# PCB_111000_New.net
KiCad netlist of a schematic drawn in EAGLE
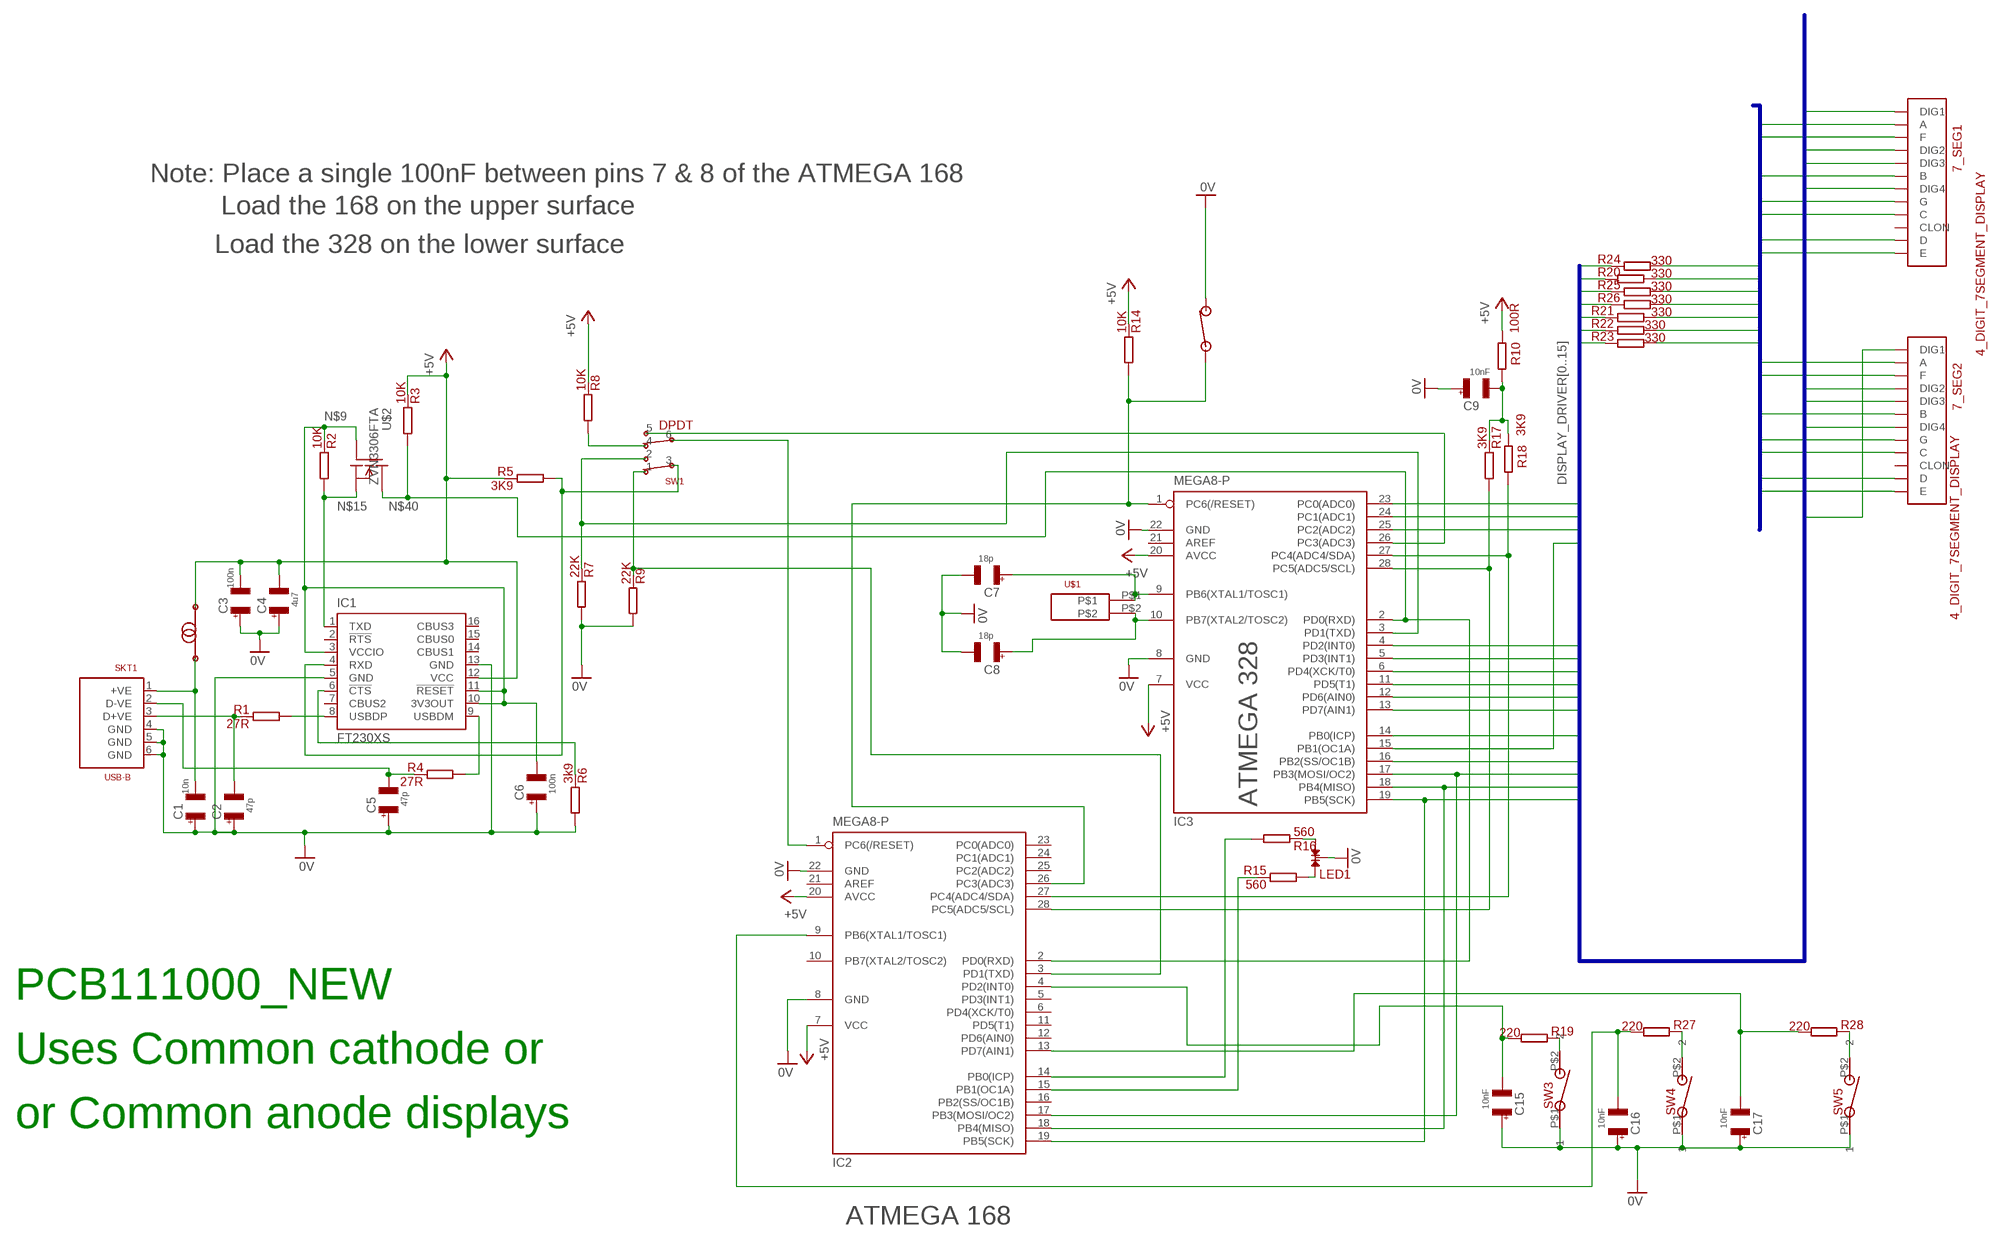
[diagram p0: schematic, sheet 1]

(export (version "E")
  (design (tool "Eeschema 10.0.6"))
  (components
    (comp (ref "7_SEG1")
      (value "4_DIGIT_7SEGMENT_DISPLAY")
      (footprint "eagle-import:4_DIGIT_7SEGMENT_DISPLAY")
      (libsource (lib "eagle-import") (part "4_DIGIT_7SEGMENT_DISPLAY"))
    )
    (comp (ref "7_SEG2")
      (value "4_DIGIT_7SEGMENT_DISPLAY")
      (footprint "eagle-import:4_DIGIT_7SEGMENT_DISPLAY")
      (libsource (lib "eagle-import") (part "4_DIGIT_7SEGMENT_DISPLAY"))
    )
    (comp (ref "C1")
      (value "10n")
      (footprint "eagle-import:1206")
      (libsource (lib "eagle-import") (part "1206C"))
    )
    (comp (ref "C2")
      (value "47p")
      (footprint "eagle-import:1206")
      (libsource (lib "eagle-import") (part "1206C"))
    )
    (comp (ref "C3")
      (value "100n")
      (footprint "eagle-import:1206")
      (libsource (lib "eagle-import") (part "1206C"))
    )
    (comp (ref "C4")
      (value "4u7")
      (footprint "eagle-import:1206")
      (libsource (lib "eagle-import") (part "1206C"))
    )
    (comp (ref "C5")
      (value "47p")
      (footprint "eagle-import:1206")
      (libsource (lib "eagle-import") (part "1206C"))
    )
    (comp (ref "C6")
      (value "100n")
      (footprint "eagle-import:1206")
      (libsource (lib "eagle-import") (part "1206C"))
    )
    (comp (ref "C7")
      (value "18p")
      (footprint "eagle-import:0805")
      (libsource (lib "eagle-import") (part "0805C"))
    )
    (comp (ref "C8")
      (value "18p")
      (footprint "eagle-import:0805")
      (libsource (lib "eagle-import") (part "0805C"))
    )
    (comp (ref "C9")
      (value "10nF")
      (footprint "eagle-import:1206")
      (libsource (lib "eagle-import") (part "1206C"))
    )
    (comp (ref "C15")
      (value "10nF")
      (footprint "eagle-import:1206")
      (libsource (lib "eagle-import") (part "1206C"))
    )
    (comp (ref "C16")
      (value "10nF")
      (footprint "eagle-import:1206")
      (libsource (lib "eagle-import") (part "1206C"))
    )
    (comp (ref "C17")
      (value "10nF")
      (footprint "eagle-import:1206")
      (libsource (lib "eagle-import") (part "1206C"))
    )
    (comp (ref "IC1")
      (value "FT230XS")
      (footprint "eagle-import:SSOP16")
      (libsource (lib "eagle-import") (part "FT230XS"))
    )
    (comp (ref "IC2")
      (value "MEGA8-P")
      (footprint "eagle-import:DIL28-3")
      (libsource (lib "eagle-import") (part "MEGA8-P"))
    )
    (comp (ref "IC3")
      (value "MEGA8-P")
      (footprint "eagle-import:DIL28-3")
      (libsource (lib "eagle-import") (part "MEGA8-P"))
    )
    (comp (ref "L1")
      (value "CHOKE")
      (footprint "eagle-import:1206")
      (libsource (lib "eagle-import") (part "CHOKE"))
    )
    (comp (ref "LED1")
      (value "LED")
      (footprint "eagle-import:CA_DUAL_LED")
      (libsource (lib "eagle-import") (part "LED"))
    )
    (comp (ref "R1")
      (value "27R")
      (footprint "eagle-import:1206")
      (libsource (lib "eagle-import") (part "1206R"))
    )
    (comp (ref "R2")
      (value "10K")
      (footprint "eagle-import:1206")
      (libsource (lib "eagle-import") (part "1206R"))
    )
    (comp (ref "R3")
      (value "10K")
      (footprint "eagle-import:1206")
      (libsource (lib "eagle-import") (part "1206R"))
    )
    (comp (ref "R4")
      (value "27R")
      (footprint "eagle-import:1206")
      (libsource (lib "eagle-import") (part "1206R"))
    )
    (comp (ref "R5")
      (value "3K9")
      (footprint "eagle-import:1206")
      (libsource (lib "eagle-import") (part "1206R"))
    )
    (comp (ref "R6")
      (value "3k9")
      (footprint "eagle-import:1206")
      (libsource (lib "eagle-import") (part "1206R"))
    )
    (comp (ref "R7")
      (value "22K")
      (footprint "eagle-import:1206")
      (libsource (lib "eagle-import") (part "1206R"))
    )
    (comp (ref "R8")
      (value "10K")
      (footprint "eagle-import:1206")
      (libsource (lib "eagle-import") (part "1206R"))
    )
    (comp (ref "R9")
      (value "22K")
      (footprint "eagle-import:1206")
      (libsource (lib "eagle-import") (part "1206R"))
    )
    (comp (ref "R10")
      (value "100R")
      (footprint "eagle-import:1206")
      (libsource (lib "eagle-import") (part "1206R"))
    )
    (comp (ref "R14")
      (value "10K")
      (footprint "eagle-import:1206")
      (libsource (lib "eagle-import") (part "1206R"))
    )
    (comp (ref "R15")
      (value "560")
      (footprint "eagle-import:1206")
      (libsource (lib "eagle-import") (part "1206R"))
    )
    (comp (ref "R16")
      (value "560")
      (footprint "eagle-import:1206")
      (libsource (lib "eagle-import") (part "1206R"))
    )
    (comp (ref "R17")
      (value "3K9")
      (footprint "eagle-import:1206")
      (libsource (lib "eagle-import") (part "1206R"))
    )
    (comp (ref "R18")
      (value "3K9")
      (footprint "eagle-import:1206")
      (libsource (lib "eagle-import") (part "1206R"))
    )
    (comp (ref "R19")
      (value "220")
      (footprint "eagle-import:1206")
      (libsource (lib "eagle-import") (part "1206R"))
    )
    (comp (ref "R20")
      (value "330")
      (footprint "eagle-import:1206")
      (libsource (lib "eagle-import") (part "1206R"))
    )
    (comp (ref "R21")
      (value "330")
      (footprint "eagle-import:1206")
      (libsource (lib "eagle-import") (part "1206R"))
    )
    (comp (ref "R22")
      (value "330")
      (footprint "eagle-import:1206")
      (libsource (lib "eagle-import") (part "1206R"))
    )
    (comp (ref "R23")
      (value "330")
      (footprint "eagle-import:1206")
      (libsource (lib "eagle-import") (part "1206R"))
    )
    (comp (ref "R24")
      (value "330")
      (footprint "eagle-import:1206")
      (libsource (lib "eagle-import") (part "1206R"))
    )
    (comp (ref "R25")
      (value "330")
      (footprint "eagle-import:1206")
      (libsource (lib "eagle-import") (part "1206R"))
    )
    (comp (ref "R26")
      (value "330")
      (footprint "eagle-import:1206")
      (libsource (lib "eagle-import") (part "1206R"))
    )
    (comp (ref "R27")
      (value "220")
      (footprint "eagle-import:1206")
      (libsource (lib "eagle-import") (part "1206R"))
    )
    (comp (ref "R28")
      (value "220")
      (footprint "eagle-import:1206")
      (libsource (lib "eagle-import") (part "1206R"))
    )
    (comp (ref "SKT1")
      (value "USB-B")
      (footprint "eagle-import:USB-B")
      (libsource (lib "eagle-import") (part "USB-B"))
    )
    (comp (ref "SW1")
      (value "DPDT")
      (footprint "eagle-import:DPDT_SWITCH")
      (libsource (lib "eagle-import") (part "DPDT"))
    )
    (comp (ref "SW2")
      (value "NO_SW")
      (footprint "eagle-import:SM_NO_PUSH_BUTTON")
      (libsource (lib "eagle-import") (part "NO_SW"))
    )
    (comp (ref "SW3")
      (value "NO_PB_1")
      (footprint "eagle-import:RE51-0711")
      (libsource (lib "eagle-import") (part "NO_PB_1"))
    )
    (comp (ref "SW4")
      (value "NO_PB_1")
      (footprint "eagle-import:RE51-0711")
      (libsource (lib "eagle-import") (part "NO_PB_1"))
    )
    (comp (ref "SW5")
      (value "NO_PB_1")
      (footprint "eagle-import:RE51-0711")
      (libsource (lib "eagle-import") (part "NO_PB_1"))
    )
    (comp (ref "U$1")
      (value "XTAL")
      (footprint "eagle-import:XTAL_VIAS")
      (libsource (lib "eagle-import") (part "XTAL"))
    )
    (comp (ref "U$2")
      (value "ZVN3306FTA")
      (footprint "eagle-import:SOT-23")
      (libsource (lib "eagle-import") (part "ZVN3306FTA"))
    )
  )
  (nets
    (net (code "2") (name "+5V") (class "Default")
      (node (ref "C3") (pin "P$2") (pinfunction "2_P$2") (pintype "bidirectional"))
      (node (ref "C4") (pin "P$2") (pinfunction "2_P$2") (pintype "bidirectional"))
      (node (ref "IC1") (pin "12") (pinfunction "VCC_12") (pintype "power_in"))
      (node (ref "IC2") (pin "20") (pinfunction "AVCC_20") (pintype "power_in"))
      (node (ref "IC2") (pin "7") (pinfunction "VCC_7") (pintype "power_in"))
      (node (ref "IC3") (pin "20") (pinfunction "AVCC_20") (pintype "power_in"))
      (node (ref "IC3") (pin "7") (pinfunction "VCC_7") (pintype "power_in"))
      (node (ref "L1") (pin "P$2") (pinfunction "2_P$2") (pintype "bidirectional"))
      (node (ref "R10") (pin "P$2") (pinfunction "P$2_P$2") (pintype "bidirectional"))
      (node (ref "R14") (pin "P$2") (pinfunction "P$2_P$2") (pintype "bidirectional"))
      (node (ref "R3") (pin "P$2") (pinfunction "P$2_P$2") (pintype "bidirectional"))
      (node (ref "R5") (pin "P$2") (pinfunction "P$2_P$2") (pintype "bidirectional"))
      (node (ref "R8") (pin "P$2") (pinfunction "P$2_P$2") (pintype "bidirectional"))
    )
    (net (code "3") (name "/DISPLAY_DRIVER0") (class "Default")
      (node (ref "IC3") (pin "15") (pinfunction "PB1(OC1A)_15") (pintype "bidirectional"))
      (node (ref "R24") (pin "P$2") (pinfunction "P$2_P$2") (pintype "bidirectional"))
    )
    (net (code "4") (name "/DISPLAY_DRIVER1") (class "Default")
      (node (ref "IC3") (pin "4") (pinfunction "PD2(INT0)_4") (pintype "bidirectional"))
      (node (ref "R20") (pin "P$2") (pinfunction "P$2_P$2") (pintype "bidirectional"))
    )
    (net (code "5") (name "/DISPLAY_DRIVER2") (class "Default")
      (node (ref "IC3") (pin "5") (pinfunction "PD3(INT1)_5") (pintype "bidirectional"))
      (node (ref "R25") (pin "P$2") (pinfunction "P$2_P$2") (pintype "bidirectional"))
    )
    (net (code "6") (name "/DISPLAY_DRIVER3") (class "Default")
      (node (ref "IC3") (pin "6") (pinfunction "PD4(XCK/T0)_6") (pintype "bidirectional"))
      (node (ref "R26") (pin "P$2") (pinfunction "P$2_P$2") (pintype "bidirectional"))
    )
    (net (code "7") (name "/DISPLAY_DRIVER4") (class "Default")
      (node (ref "IC3") (pin "11") (pinfunction "PD5(T1)_11") (pintype "bidirectional"))
      (node (ref "R21") (pin "P$2") (pinfunction "P$2_P$2") (pintype "bidirectional"))
    )
    (net (code "8") (name "/DISPLAY_DRIVER5") (class "Default")
      (node (ref "IC3") (pin "12") (pinfunction "PD6(AIN0)_12") (pintype "bidirectional"))
      (node (ref "R22") (pin "P$2") (pinfunction "P$2_P$2") (pintype "bidirectional"))
    )
    (net (code "9") (name "/DISPLAY_DRIVER6") (class "Default")
      (node (ref "IC3") (pin "13") (pinfunction "PD7(AIN1)_13") (pintype "bidirectional"))
      (node (ref "R23") (pin "P$2") (pinfunction "P$2_P$2") (pintype "bidirectional"))
    )
    (net (code "10") (name "/DISPLAY_DRIVER8") (class "Default")
      (node (ref "7_SEG2") (pin "P$12") (pinfunction "DIG1_P$12") (pintype "bidirectional"))
      (node (ref "IC3") (pin "14") (pinfunction "PB0(ICP)_14") (pintype "bidirectional"))
    )
    (net (code "11") (name "/DISPLAY_DRIVER9") (class "Default")
      (node (ref "7_SEG2") (pin "P$9") (pinfunction "DIG2_P$9") (pintype "bidirectional"))
      (node (ref "IC3") (pin "16") (pinfunction "PB2(SS/OC1B)_16") (pintype "bidirectional"))
    )
    (net (code "12") (name "/DISPLAY_DRIVER10") (class "Default")
      (node (ref "7_SEG2") (pin "P$8") (pinfunction "DIG3_P$8") (pintype "bidirectional"))
      (node (ref "IC2") (pin "17") (pinfunction "PB3(MOSI/OC2)_17") (pintype "bidirectional"))
      (node (ref "IC3") (pin "17") (pinfunction "PB3(MOSI/OC2)_17") (pintype "bidirectional"))
    )
    (net (code "13") (name "/DISPLAY_DRIVER11") (class "Default")
      (node (ref "7_SEG2") (pin "P$6") (pinfunction "DIG4_P$6") (pintype "bidirectional"))
      (node (ref "IC2") (pin "18") (pinfunction "PB4(MISO)_18") (pintype "bidirectional"))
      (node (ref "IC3") (pin "18") (pinfunction "PB4(MISO)_18") (pintype "bidirectional"))
    )
    (net (code "14") (name "/DISPLAY_DRIVER12") (class "Default")
      (node (ref "7_SEG1") (pin "P$12") (pinfunction "DIG1_P$12") (pintype "bidirectional"))
      (node (ref "IC2") (pin "19") (pinfunction "PB5(SCK)_19") (pintype "bidirectional"))
      (node (ref "IC3") (pin "19") (pinfunction "PB5(SCK)_19") (pintype "bidirectional"))
    )
    (net (code "15") (name "/DISPLAY_DRIVER13") (class "Default")
      (node (ref "7_SEG1") (pin "P$9") (pinfunction "DIG2_P$9") (pintype "bidirectional"))
      (node (ref "IC3") (pin "23") (pinfunction "PC0(ADC0)_23") (pintype "bidirectional"))
    )
    (net (code "16") (name "/DISPLAY_DRIVER14") (class "Default")
      (node (ref "7_SEG1") (pin "P$8") (pinfunction "DIG3_P$8") (pintype "bidirectional"))
      (node (ref "IC3") (pin "24") (pinfunction "PC1(ADC1)_24") (pintype "bidirectional"))
    )
    (net (code "17") (name "/DISPLAY_DRIVER15") (class "Default")
      (node (ref "7_SEG1") (pin "P$6") (pinfunction "DIG4_P$6") (pintype "bidirectional"))
      (node (ref "IC3") (pin "25") (pinfunction "PC2(ADC2)_25") (pintype "bidirectional"))
    )
    (net (code "19") (name "/N$9") (class "Default")
      (node (ref "C6") (pin "P$2") (pinfunction "2_P$2") (pintype "bidirectional"))
      (node (ref "IC1") (pin "10") (pinfunction "3V3OUT_10") (pintype "output"))
      (node (ref "IC1") (pin "11") (pinfunction "~{RESET}_11") (pintype "input"))
      (node (ref "IC1") (pin "3") (pinfunction "VCCIO_3") (pintype "power_in"))
      (node (ref "R2") (pin "P$2") (pinfunction "P$2_P$2") (pintype "bidirectional"))
      (node (ref "U$2") (pin "3") (pinfunction "G_3") (pintype "passive"))
    )
    (net (code "20") (name "/N$15") (class "Default")
      (node (ref "IC1") (pin "1") (pinfunction "TXD_1") (pintype "output"))
      (node (ref "R2") (pin "P$1") (pinfunction "P$1_P$1") (pintype "bidirectional"))
      (node (ref "U$2") (pin "2") (pinfunction "S_2") (pintype "passive"))
    )
    (net (code "21") (name "/N$40") (class "Default")
      (node (ref "IC2") (pin "2") (pinfunction "PD0(RXD)_2") (pintype "bidirectional"))
      (node (ref "IC3") (pin "2") (pinfunction "PD0(RXD)_2") (pintype "bidirectional"))
      (node (ref "R3") (pin "P$1") (pinfunction "P$1_P$1") (pintype "bidirectional"))
      (node (ref "U$2") (pin "1") (pinfunction "D_1") (pintype "passive"))
    )
    (net (code "22") (name "/SEVEN_SEG0") (class "Default")
      (node (ref "7_SEG1") (pin "P$11") (pinfunction "A_P$11") (pintype "bidirectional"))
      (node (ref "7_SEG2") (pin "P$11") (pinfunction "A_P$11") (pintype "bidirectional"))
      (node (ref "R24") (pin "P$1") (pinfunction "P$1_P$1") (pintype "bidirectional"))
    )
    (net (code "23") (name "/SEVEN_SEG1") (class "Default")
      (node (ref "7_SEG1") (pin "P$7") (pinfunction "B_P$7") (pintype "bidirectional"))
      (node (ref "7_SEG2") (pin "P$7") (pinfunction "B_P$7") (pintype "bidirectional"))
      (node (ref "R20") (pin "P$1") (pinfunction "P$1_P$1") (pintype "bidirectional"))
    )
    (net (code "24") (name "/SEVEN_SEG2") (class "Default")
      (node (ref "7_SEG1") (pin "P$4") (pinfunction "C_P$4") (pintype "bidirectional"))
      (node (ref "7_SEG2") (pin "P$4") (pinfunction "C_P$4") (pintype "bidirectional"))
      (node (ref "R25") (pin "P$1") (pinfunction "P$1_P$1") (pintype "bidirectional"))
    )
    (net (code "25") (name "/SEVEN_SEG3") (class "Default")
      (node (ref "7_SEG1") (pin "P$2") (pinfunction "D_P$2") (pintype "bidirectional"))
      (node (ref "7_SEG2") (pin "P$2") (pinfunction "D_P$2") (pintype "bidirectional"))
      (node (ref "R26") (pin "P$1") (pinfunction "P$1_P$1") (pintype "bidirectional"))
    )
    (net (code "26") (name "/SEVEN_SEG4") (class "Default")
      (node (ref "7_SEG1") (pin "P$1") (pinfunction "E_P$1") (pintype "bidirectional"))
      (node (ref "7_SEG2") (pin "P$1") (pinfunction "E_P$1") (pintype "bidirectional"))
      (node (ref "R21") (pin "P$1") (pinfunction "P$1_P$1") (pintype "bidirectional"))
    )
    (net (code "27") (name "/SEVEN_SEG5") (class "Default")
      (node (ref "7_SEG1") (pin "P$10") (pinfunction "F_P$10") (pintype "bidirectional"))
      (node (ref "7_SEG2") (pin "P$10") (pinfunction "F_P$10") (pintype "bidirectional"))
      (node (ref "R22") (pin "P$1") (pinfunction "P$1_P$1") (pintype "bidirectional"))
    )
    (net (code "28") (name "/SEVEN_SEG6") (class "Default")
      (node (ref "7_SEG1") (pin "P$5") (pinfunction "G_P$5") (pintype "bidirectional"))
      (node (ref "7_SEG2") (pin "P$5") (pinfunction "G_P$5") (pintype "bidirectional"))
      (node (ref "R23") (pin "P$1") (pinfunction "P$1_P$1") (pintype "bidirectional"))
    )
    (net (code "29") (name "0V") (class "Default")
      (node (ref "C1") (pin "P$1") (pinfunction "1_P$1") (pintype "bidirectional"))
      (node (ref "C15") (pin "P$1") (pinfunction "1_P$1") (pintype "bidirectional"))
      (node (ref "C16") (pin "P$1") (pinfunction "1_P$1") (pintype "bidirectional"))
      (node (ref "C17") (pin "P$1") (pinfunction "1_P$1") (pintype "bidirectional"))
      (node (ref "C2") (pin "P$1") (pinfunction "1_P$1") (pintype "bidirectional"))
      (node (ref "C3") (pin "P$1") (pinfunction "1_P$1") (pintype "bidirectional"))
      (node (ref "C4") (pin "P$1") (pinfunction "1_P$1") (pintype "bidirectional"))
      (node (ref "C5") (pin "P$1") (pinfunction "1_P$1") (pintype "bidirectional"))
      (node (ref "C6") (pin "P$1") (pinfunction "1_P$1") (pintype "bidirectional"))
      (node (ref "C7") (pin "2") (pinfunction "2_2") (pintype "bidirectional"))
      (node (ref "C8") (pin "2") (pinfunction "2_2") (pintype "bidirectional"))
      (node (ref "C9") (pin "P$1") (pinfunction "1_P$1") (pintype "bidirectional"))
      (node (ref "IC1") (pin "13") (pinfunction "GND_13") (pintype "power_in"))
      (node (ref "IC1") (pin "5") (pinfunction "GND_5") (pintype "power_in"))
      (node (ref "IC2") (pin "22") (pinfunction "GND_22") (pintype "power_in"))
      (node (ref "IC2") (pin "8") (pinfunction "GND_8") (pintype "power_in"))
      (node (ref "IC3") (pin "22") (pinfunction "GND_22") (pintype "power_in"))
      (node (ref "IC3") (pin "8") (pinfunction "GND_8") (pintype "power_in"))
      (node (ref "LED1") (pin "2") (pinfunction "2_2") (pintype "bidirectional"))
      (node (ref "R6") (pin "P$1") (pinfunction "P$1_P$1") (pintype "bidirectional"))
      (node (ref "R7") (pin "P$1") (pinfunction "P$1_P$1") (pintype "bidirectional"))
      (node (ref "R9") (pin "P$1") (pinfunction "P$1_P$1") (pintype "bidirectional"))
      (node (ref "SKT1") (pin "4") (pinfunction "GND_4") (pintype "bidirectional"))
      (node (ref "SKT1") (pin "5") (pinfunction "GND_5") (pintype "bidirectional"))
      (node (ref "SKT1") (pin "6") (pinfunction "GND_6") (pintype "bidirectional"))
      (node (ref "SW2") (pin "P$2") (pinfunction "2_P$2") (pintype "bidirectional"))
      (node (ref "SW3") (pin "P$1") (pinfunction "1_P$1") (pintype "bidirectional"))
      (node (ref "SW4") (pin "P$1") (pinfunction "1_P$1") (pintype "bidirectional"))
      (node (ref "SW5") (pin "P$1") (pinfunction "1_P$1") (pintype "bidirectional"))
    )
    (net (code "30") (name "Net-(C1-2)") (class "Default")
      (node (ref "C1") (pin "P$2") (pinfunction "2_P$2") (pintype "bidirectional"))
      (node (ref "L1") (pin "P$1") (pinfunction "1_P$1") (pintype "bidirectional"))
      (node (ref "SKT1") (pin "1") (pinfunction "+VE_1") (pintype "bidirectional"))
    )
    (net (code "31") (name "Net-(C2-2)") (class "Default")
      (node (ref "C2") (pin "P$2") (pinfunction "2_P$2") (pintype "bidirectional"))
      (node (ref "R1") (pin "P$2") (pinfunction "P$2_P$2") (pintype "bidirectional"))
      (node (ref "SKT1") (pin "3") (pinfunction "D+VE_3") (pintype "bidirectional"))
    )
    (net (code "32") (name "Net-(C5-2)") (class "Default")
      (node (ref "C5") (pin "P$2") (pinfunction "2_P$2") (pintype "bidirectional"))
      (node (ref "R4") (pin "P$2") (pinfunction "P$2_P$2") (pintype "bidirectional"))
      (node (ref "SKT1") (pin "2") (pinfunction "D-VE_2") (pintype "bidirectional"))
    )
    (net (code "33") (name "Net-(C9-2)") (class "Default")
      (node (ref "C9") (pin "P$2") (pinfunction "2_P$2") (pintype "bidirectional"))
      (node (ref "R10") (pin "P$1") (pinfunction "P$1_P$1") (pintype "bidirectional"))
      (node (ref "R17") (pin "P$2") (pinfunction "P$2_P$2") (pintype "bidirectional"))
      (node (ref "R18") (pin "P$2") (pinfunction "P$2_P$2") (pintype "bidirectional"))
    )
    (net (code "34") (name "Net-(C15-2)") (class "Default")
      (node (ref "C15") (pin "P$2") (pinfunction "2_P$2") (pintype "bidirectional"))
      (node (ref "IC2") (pin "4") (pinfunction "PD2(INT0)_4") (pintype "bidirectional"))
      (node (ref "R19") (pin "P$1") (pinfunction "P$1_P$1") (pintype "bidirectional"))
    )
    (net (code "35") (name "Net-(C16-2)") (class "Default")
      (node (ref "C16") (pin "P$2") (pinfunction "2_P$2") (pintype "bidirectional"))
      (node (ref "IC2") (pin "9") (pinfunction "PB6(XTAL1/TOSC1)_9") (pintype "bidirectional"))
      (node (ref "R27") (pin "P$1") (pinfunction "P$1_P$1") (pintype "bidirectional"))
    )
    (net (code "36") (name "Net-(C17-2)") (class "Default")
      (node (ref "C17") (pin "P$2") (pinfunction "2_P$2") (pintype "bidirectional"))
      (node (ref "IC2") (pin "13") (pinfunction "PD7(AIN1)_13") (pintype "bidirectional"))
      (node (ref "R28") (pin "P$1") (pinfunction "P$1_P$1") (pintype "bidirectional"))
    )
    (net (code "37") (name "Net-(IC1-RXD)") (class "Default")
      (node (ref "IC1") (pin "4") (pinfunction "RXD_4") (pintype "input"))
      (node (ref "R5") (pin "P$1") (pinfunction "P$1_P$1") (pintype "bidirectional"))
      (node (ref "SW1") (pin "3") (pinfunction "3_3") (pintype "bidirectional"))
    )
    (net (code "38") (name "Net-(IC1-USBDM)") (class "Default")
      (node (ref "IC1") (pin "9") (pinfunction "USBDM_9") (pintype "input"))
      (node (ref "R4") (pin "P$1") (pinfunction "P$1_P$1") (pintype "bidirectional"))
    )
    (net (code "39") (name "Net-(IC1-USBDP)") (class "Default")
      (node (ref "IC1") (pin "8") (pinfunction "USBDP_8") (pintype "input"))
      (node (ref "R1") (pin "P$1") (pinfunction "P$1_P$1") (pintype "bidirectional"))
    )
    (net (code "40") (name "Net-(IC1-~{CTS})") (class "Default")
      (node (ref "IC1") (pin "6") (pinfunction "~{CTS}_6") (pintype "input"))
      (node (ref "R6") (pin "P$2") (pinfunction "P$2_P$2") (pintype "bidirectional"))
    )
    (net (code "41") (name "Net-(IC2-PB0(ICP))") (class "Default")
      (node (ref "IC2") (pin "14") (pinfunction "PB0(ICP)_14") (pintype "bidirectional"))
      (node (ref "R16") (pin "P$1") (pinfunction "P$1_P$1") (pintype "bidirectional"))
    )
    (net (code "42") (name "Net-(IC2-PB1(OC1A))") (class "Default")
      (node (ref "IC2") (pin "15") (pinfunction "PB1(OC1A)_15") (pintype "bidirectional"))
      (node (ref "R15") (pin "P$2") (pinfunction "P$2_P$2") (pintype "bidirectional"))
    )
    (net (code "43") (name "Net-(IC2-PC3(ADC3))") (class "Default")
      (node (ref "IC2") (pin "26") (pinfunction "PC3(ADC3)_26") (pintype "bidirectional"))
      (node (ref "IC3") (pin "1") (pinfunction "PC6(/RESET)_1") (pintype "bidirectional"))
      (node (ref "R14") (pin "P$1") (pinfunction "P$1_P$1") (pintype "bidirectional"))
      (node (ref "SW2") (pin "P$1") (pinfunction "1_P$1") (pintype "bidirectional"))
    )
    (net (code "44") (name "Net-(IC2-PC4(ADC4{slash}SDA))") (class "Default")
      (node (ref "IC2") (pin "27") (pinfunction "PC4(ADC4/SDA)_27") (pintype "bidirectional"))
      (node (ref "IC3") (pin "27") (pinfunction "PC4(ADC4/SDA)_27") (pintype "bidirectional"))
      (node (ref "R18") (pin "P$1") (pinfunction "P$1_P$1") (pintype "bidirectional"))
    )
    (net (code "45") (name "Net-(IC2-PC5(ADC5{slash}SCL))") (class "Default")
      (node (ref "IC2") (pin "28") (pinfunction "PC5(ADC5/SCL)_28") (pintype "bidirectional"))
      (node (ref "IC3") (pin "28") (pinfunction "PC5(ADC5/SCL)_28") (pintype "bidirectional"))
      (node (ref "R17") (pin "P$1") (pinfunction "P$1_P$1") (pintype "bidirectional"))
    )
    (net (code "46") (name "Net-(IC2-PC6({slash}RESET))") (class "Default")
      (node (ref "IC2") (pin "1") (pinfunction "PC6(/RESET)_1") (pintype "bidirectional"))
      (node (ref "SW1") (pin "6") (pinfunction "6_6") (pintype "bidirectional"))
    )
    (net (code "47") (name "Net-(IC2-PD1(TXD))") (class "Default")
      (node (ref "IC2") (pin "3") (pinfunction "PD1(TXD)_3") (pintype "bidirectional"))
      (node (ref "R9") (pin "P$2") (pinfunction "P$2_P$2") (pintype "bidirectional"))
      (node (ref "SW1") (pin "1") (pinfunction "1_1") (pintype "bidirectional"))
    )
    (net (code "48") (name "Net-(IC3-PB6(XTAL1{slash}TOSC1))") (class "Default")
      (node (ref "C7") (pin "1") (pinfunction "1_1") (pintype "bidirectional"))
      (node (ref "IC3") (pin "9") (pinfunction "PB6(XTAL1/TOSC1)_9") (pintype "bidirectional"))
      (node (ref "U$1") (pin "P$1") (pinfunction "P$1_P$1") (pintype "bidirectional"))
    )
    (net (code "49") (name "Net-(IC3-PB7(XTAL2{slash}TOSC2))") (class "Default")
      (node (ref "C8") (pin "1") (pinfunction "1_1") (pintype "bidirectional"))
      (node (ref "IC3") (pin "10") (pinfunction "PB7(XTAL2/TOSC2)_10") (pintype "bidirectional"))
      (node (ref "U$1") (pin "P$2") (pinfunction "P$2_P$2") (pintype "bidirectional"))
    )
    (net (code "50") (name "Net-(IC3-PC3(ADC3))") (class "Default")
      (node (ref "IC3") (pin "26") (pinfunction "PC3(ADC3)_26") (pintype "bidirectional"))
      (node (ref "SW1") (pin "5") (pinfunction "5_5") (pintype "bidirectional"))
    )
    (net (code "51") (name "Net-(IC3-PD1(TXD))") (class "Default")
      (node (ref "IC3") (pin "3") (pinfunction "PD1(TXD)_3") (pintype "bidirectional"))
      (node (ref "R7") (pin "P$2") (pinfunction "P$2_P$2") (pintype "bidirectional"))
      (node (ref "SW1") (pin "2") (pinfunction "2_2") (pintype "bidirectional"))
    )
    (net (code "52") (name "Net-(LED1-Pad1)") (class "Default")
      (node (ref "LED1") (pin "1") (pinfunction "1_1") (pintype "bidirectional"))
      (node (ref "R15") (pin "P$1") (pinfunction "P$1_P$1") (pintype "bidirectional"))
    )
    (net (code "53") (name "Net-(LED1-Pad3)") (class "Default")
      (node (ref "LED1") (pin "3") (pinfunction "3_3") (pintype "bidirectional"))
      (node (ref "R16") (pin "P$2") (pinfunction "P$2_P$2") (pintype "bidirectional"))
    )
    (net (code "54") (name "Net-(R8-PadP$1)") (class "Default")
      (node (ref "R8") (pin "P$1") (pinfunction "P$1_P$1") (pintype "bidirectional"))
      (node (ref "SW1") (pin "4") (pinfunction "4_4") (pintype "bidirectional"))
    )
    (net (code "55") (name "Net-(SW3-2)") (class "Default")
      (node (ref "R19") (pin "P$2") (pinfunction "P$2_P$2") (pintype "bidirectional"))
      (node (ref "SW3") (pin "P$2") (pinfunction "2_P$2") (pintype "bidirectional"))
    )
    (net (code "56") (name "Net-(SW4-2)") (class "Default")
      (node (ref "R27") (pin "P$2") (pinfunction "P$2_P$2") (pintype "bidirectional"))
      (node (ref "SW4") (pin "P$2") (pinfunction "2_P$2") (pintype "bidirectional"))
    )
    (net (code "57") (name "Net-(SW5-2)") (class "Default")
      (node (ref "R28") (pin "P$2") (pinfunction "P$2_P$2") (pintype "bidirectional"))
      (node (ref "SW5") (pin "P$2") (pinfunction "2_P$2") (pintype "bidirectional"))
    )
    (net (code "58") (name "unconnected-(7_SEG1-CLON-PadP$3)") (class "Default")
      (node (ref "7_SEG1") (pin "P$3") (pinfunction "CLON_P$3") (pintype "bidirectional"))
    )
    (net (code "59") (name "unconnected-(7_SEG2-CLON-PadP$3)") (class "Default")
      (node (ref "7_SEG2") (pin "P$3") (pinfunction "CLON_P$3") (pintype "bidirectional"))
    )
    (net (code "60") (name "unconnected-(IC1-CBUS0-Pad15)") (class "Default")
      (node (ref "IC1") (pin "15") (pinfunction "CBUS0_15") (pintype "bidirectional"))
    )
    (net (code "61") (name "unconnected-(IC1-CBUS1-Pad14)") (class "Default")
      (node (ref "IC1") (pin "14") (pinfunction "CBUS1_14") (pintype "bidirectional"))
    )
    (net (code "62") (name "unconnected-(IC1-CBUS2-Pad7)") (class "Default")
      (node (ref "IC1") (pin "7") (pinfunction "CBUS2_7") (pintype "bidirectional"))
    )
    (net (code "63") (name "unconnected-(IC1-CBUS3-Pad16)") (class "Default")
      (node (ref "IC1") (pin "16") (pinfunction "CBUS3_16") (pintype "bidirectional"))
    )
    (net (code "64") (name "unconnected-(IC1-~{RTS}-Pad2)") (class "Default")
      (node (ref "IC1") (pin "2") (pinfunction "~{RTS}_2") (pintype "output"))
    )
    (net (code "65") (name "unconnected-(IC2-AREF-Pad21)") (class "Default")
      (node (ref "IC2") (pin "21") (pinfunction "AREF_21") (pintype "passive"))
    )
    (net (code "66") (name "unconnected-(IC2-PB2(SS{slash}OC1B)-Pad16)") (class "Default")
      (node (ref "IC2") (pin "16") (pinfunction "PB2(SS/OC1B)_16") (pintype "bidirectional"))
    )
    (net (code "67") (name "unconnected-(IC2-PB7(XTAL2{slash}TOSC2)-Pad10)") (class "Default")
      (node (ref "IC2") (pin "10") (pinfunction "PB7(XTAL2/TOSC2)_10") (pintype "bidirectional"))
    )
    (net (code "68") (name "unconnected-(IC2-PC0(ADC0)-Pad23)") (class "Default")
      (node (ref "IC2") (pin "23") (pinfunction "PC0(ADC0)_23") (pintype "bidirectional"))
    )
    (net (code "69") (name "unconnected-(IC2-PC1(ADC1)-Pad24)") (class "Default")
      (node (ref "IC2") (pin "24") (pinfunction "PC1(ADC1)_24") (pintype "bidirectional"))
    )
    (net (code "70") (name "unconnected-(IC2-PC2(ADC2)-Pad25)") (class "Default")
      (node (ref "IC2") (pin "25") (pinfunction "PC2(ADC2)_25") (pintype "bidirectional"))
    )
    (net (code "71") (name "unconnected-(IC2-PD3(INT1)-Pad5)") (class "Default")
      (node (ref "IC2") (pin "5") (pinfunction "PD3(INT1)_5") (pintype "bidirectional"))
    )
    (net (code "72") (name "unconnected-(IC2-PD4(XCK{slash}T0)-Pad6)") (class "Default")
      (node (ref "IC2") (pin "6") (pinfunction "PD4(XCK/T0)_6") (pintype "bidirectional"))
    )
    (net (code "73") (name "unconnected-(IC2-PD5(T1)-Pad11)") (class "Default")
      (node (ref "IC2") (pin "11") (pinfunction "PD5(T1)_11") (pintype "bidirectional"))
    )
    (net (code "74") (name "unconnected-(IC2-PD6(AIN0)-Pad12)") (class "Default")
      (node (ref "IC2") (pin "12") (pinfunction "PD6(AIN0)_12") (pintype "bidirectional"))
    )
    (net (code "75") (name "unconnected-(IC3-AREF-Pad21)") (class "Default")
      (node (ref "IC3") (pin "21") (pinfunction "AREF_21") (pintype "passive"))
    )
  )
)
